# STM32.net
KiCad netlist of a schematic drawn in Altium Designer
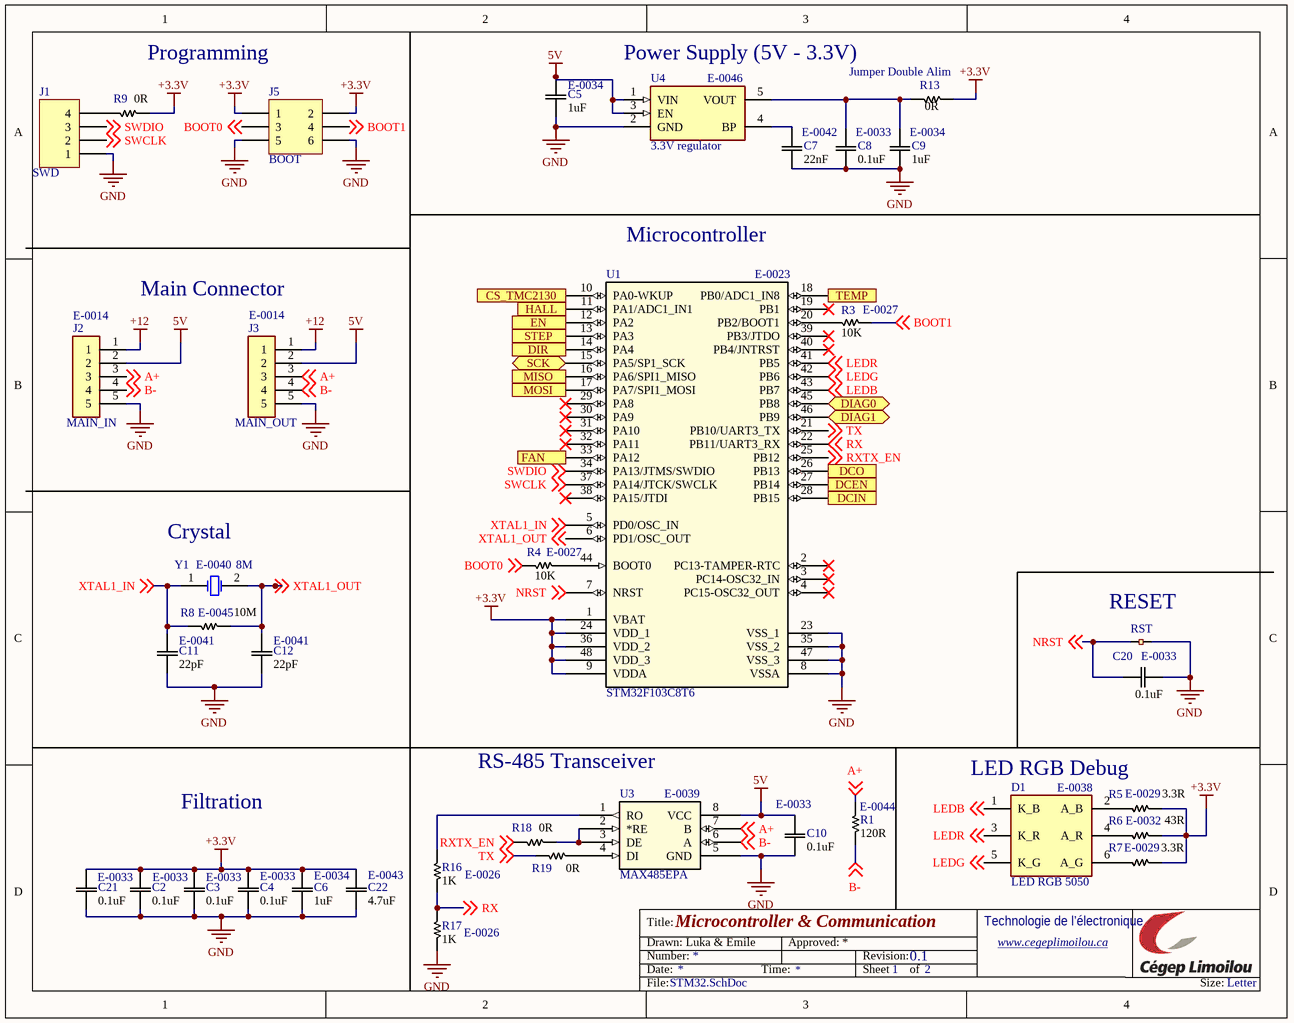
[diagram p0: STM32.SchDoc]

(export (version "E")
  (design (tool "Eeschema 10.0.6"))
  (components
    (comp (ref "C2")
      (value "0.1uF")
      (footprint "0603")
      (description "0.1uF Capacitor 0603 SMD")
      (fields
        (field (name "MANUFACTURER_PART_NUMBER") "C0603C104Z3VACTU")
        (field (name "EXCEL NUMBER") "E-0033")
        (field (name "Comment") "E-0033")
        (field (name "COPYRIGHT") "Luka & Émile")
      )
      (libsource (lib "Motor Driver") (part "E-0033"))
    )
    (comp (ref "C3")
      (value "0.1uF")
      (footprint "0603")
      (description "0.1uF Capacitor 0603 SMD")
      (fields
        (field (name "MANUFACTURER_PART_NUMBER") "C0603C104Z3VACTU")
        (field (name "EXCEL NUMBER") "E-0033")
        (field (name "Comment") "E-0033")
        (field (name "COPYRIGHT") "Luka & Émile")
      )
      (libsource (lib "Motor Driver") (part "E-0033"))
    )
    (comp (ref "C4")
      (value "0.1uF")
      (footprint "0603")
      (description "0.1uF Capacitor 0603 SMD")
      (fields
        (field (name "MANUFACTURER_PART_NUMBER") "C0603C104Z3VACTU")
        (field (name "EXCEL NUMBER") "E-0033")
        (field (name "Comment") "E-0033")
        (field (name "COPYRIGHT") "Luka & Émile")
      )
      (libsource (lib "Motor Driver") (part "E-0033"))
    )
    (comp (ref "C5")
      (value "1uF")
      (footprint "0603")
      (description "1uf Capacitor 0603 SMD")
      (fields
        (field (name "MANUFACTURER_PART_NUMBER") "CL10A105KA8NNNC")
        (field (name "EXCEL NUMBER") "E-0034")
        (field (name "Comment") "E-0034")
        (field (name "COPYRIGHT") "Luka & Émile")
      )
      (libsource (lib "Motor Driver") (part "E-0034"))
    )
    (comp (ref "C6")
      (value "1uF")
      (footprint "0603")
      (description "1uf Capacitor 0603 SMD")
      (fields
        (field (name "MANUFACTURER_PART_NUMBER") "CL10A105KA8NNNC")
        (field (name "EXCEL NUMBER") "E-0034")
        (field (name "Comment") "E-0034")
        (field (name "COPYRIGHT") "Luka & Émile")
      )
      (libsource (lib "Motor Driver") (part "E-0034"))
    )
    (comp (ref "C7")
      (value "22nF")
      (footprint "0603")
      (description "22nF Capacitor 0603 SMD")
      (fields
        (field (name "MANUFACTURER_PART_NUMBER") "C0603C223K1RACTU")
        (field (name "EXCEL NUMBER") "E-0042")
        (field (name "Comment") "E-0042")
        (field (name "COPYRIGHT") "Luka & Émile")
      )
      (libsource (lib "Motor Driver") (part "E-0042"))
    )
    (comp (ref "C8")
      (value "0.1uF")
      (footprint "0603")
      (description "0.1uF Capacitor 0603 SMD")
      (fields
        (field (name "MANUFACTURER_PART_NUMBER") "C0603C104Z3VACTU")
        (field (name "EXCEL NUMBER") "E-0033")
        (field (name "Comment") "E-0033")
        (field (name "COPYRIGHT") "Luka & Émile")
      )
      (libsource (lib "Motor Driver") (part "E-0033"))
    )
    (comp (ref "C9")
      (value "1uF")
      (footprint "0603")
      (description "1uf Capacitor 0603 SMD")
      (fields
        (field (name "MANUFACTURER_PART_NUMBER") "CL10A105KA8NNNC")
        (field (name "EXCEL NUMBER") "E-0034")
        (field (name "Comment") "E-0034")
        (field (name "COPYRIGHT") "Luka & Émile")
      )
      (libsource (lib "Motor Driver") (part "E-0034"))
    )
    (comp (ref "C10")
      (value "0.1uF")
      (footprint "0603")
      (description "0.1uF Capacitor 0603 SMD")
      (fields
        (field (name "MANUFACTURER_PART_NUMBER") "C0603C104Z3VACTU")
        (field (name "EXCEL NUMBER") "E-0033")
        (field (name "Comment") "E-0033")
        (field (name "COPYRIGHT") "Luka & Émile")
      )
      (libsource (lib "Motor Driver") (part "E-0033"))
    )
    (comp (ref "C11")
      (value "22pF")
      (footprint "0603")
      (description "22pF Capacitor 0603 SMD")
      (fields
        (field (name "MANUFACTURER_PART_NUMBER") "C0603C220J1GACTU")
        (field (name "EXCEL NUMBER") "E-0041")
        (field (name "Comment") "E-0041")
        (field (name "COPYRIGHT") "Luka & Émile")
      )
      (libsource (lib "Motor Driver") (part "E-0041"))
    )
    (comp (ref "C12")
      (value "22pF")
      (footprint "0603")
      (description "22pF Capacitor 0603 SMD")
      (fields
        (field (name "MANUFACTURER_PART_NUMBER") "C0603C220J1GACTU")
        (field (name "EXCEL NUMBER") "E-0041")
        (field (name "Comment") "E-0041")
        (field (name "COPYRIGHT") "Luka & Émile")
      )
      (libsource (lib "Motor Driver") (part "E-0041"))
    )
    (comp (ref "C20")
      (value "0.1uF")
      (footprint "0603")
      (description "0.1uF Capacitor 0603 SMD")
      (fields
        (field (name "MANUFACTURER_PART_NUMBER") "C0603C104Z3VACTU")
        (field (name "EXCEL NUMBER") "E-0033")
        (field (name "Comment") "E-0033")
        (field (name "COPYRIGHT") "Luka & Émile")
      )
      (libsource (lib "Motor Driver") (part "E-0033"))
    )
    (comp (ref "C21")
      (value "0.1uF")
      (footprint "0603")
      (description "0.1uF Capacitor 0603 SMD")
      (fields
        (field (name "MANUFACTURER_PART_NUMBER") "C0603C104Z3VACTU")
        (field (name "EXCEL NUMBER") "E-0033")
        (field (name "Comment") "E-0033")
        (field (name "COPYRIGHT") "Luka & Émile")
      )
      (libsource (lib "Motor Driver") (part "E-0033"))
    )
    (comp (ref "C22")
      (value "4.7uF")
      (footprint "0603")
      (description "4.7uF Capacitor 0603 SMD")
      (fields
        (field (name "MANUFACTURER_PART_NUMBER") "C0603C475K9PACTU")
        (field (name "EXCEL NUMBER") "E-0043")
        (field (name "Comment") "E-0043")
        (field (name "COPYRIGHT") "Luka & Émile")
      )
      (libsource (lib "Motor Driver") (part "E-0043"))
    )
    (comp (ref "D1")
      (value "LED RGB 5050")
      (footprint "LED 5050")
      (fields
        (field (name "MANUFACTURER_PART_NUMBER") "150505M173300")
        (field (name "EXCEL NUMBER") "E-0038")
        (field (name "COPYRIGHT") "Luka & Émile")
      )
      (libsource (lib "Motor Driver") (part "E-0038"))
    )
    (comp (ref "J1")
      (value "SWD")
      (footprint "HDR1X4")
      (description "Header, 4POS")
      (fields
        (field (name "MANUFACTURER_PART_NUMBER") "61300411121")
        (field (name "COPYRIGHT") "Luka & Émile")
      )
      (libsource (lib "Motor Driver") (part "E-0048"))
    )
    (comp (ref "J2")
      (value "MAIN_IN")
      (footprint "JST 5POS 2.5mm 90°")
      (description "Connector JST 5POS")
      (fields
        (field (name "MANUFACTURER_PART_NUMBER") "S5B-XH-A-1(LF)(SN)")
        (field (name "EXCEL NUMBER") "E-0014")
        (field (name "COPYRIGHT") "Luka & Émile")
      )
      (libsource (lib "Motor Driver") (part "E-0014"))
    )
    (comp (ref "J3")
      (value "MAIN_OUT")
      (footprint "JST 5POS 2.5mm 90°")
      (description "Connector JST 5POS")
      (fields
        (field (name "MANUFACTURER_PART_NUMBER") "S5B-XH-A-1(LF)(SN)")
        (field (name "EXCEL NUMBER") "E-0014")
        (field (name "COPYRIGHT") "Luka & Émile")
      )
      (libsource (lib "Motor Driver") (part "E-0014"))
    )
    (comp (ref "J5")
      (value "BOOT")
      (footprint "Header 3x2 1.27mm SMD")
      (description "Header, 3-Pin, Dual row")
      (fields
        (field (name "MANUFACTURER_PART_NUMBER") "GRPB032VWVN-RC")
        (field (name "COPYRIGHT") "Luka & Émile")
      )
      (libsource (lib "Motor Driver") (part "E-0049"))
    )
    (comp (ref "R1")
      (value "120R")
      (footprint "0603")
      (description "120R Resistor 0603 SMD")
      (fields
        (field (name "MANUFACTURER_PART_NUMBER") "KDV06FR120ET")
        (field (name "EXCEL NUMBER") "E-0044")
        (field (name "Comment") "E-0044")
        (field (name "COPYRIGHT") "Luka & Émile")
      )
      (libsource (lib "Motor Driver") (part "E-0044"))
    )
    (comp (ref "R3")
      (value "10K")
      (footprint "0603")
      (description "10K Resistor 0603 SMD")
      (fields
        (field (name "MANUFACTURER_PART_NUMBER") "RMCF0603JT10K0")
        (field (name "EXCEL NUMBER") "E-0027")
        (field (name "Comment") "E-0027")
        (field (name "COPYRIGHT") "Luka & Émile")
      )
      (libsource (lib "Motor Driver") (part "E-0027"))
    )
    (comp (ref "R4")
      (value "10K")
      (footprint "0603")
      (description "10K Resistor 0603 SMD")
      (fields
        (field (name "MANUFACTURER_PART_NUMBER") "RMCF0603JT10K0")
        (field (name "EXCEL NUMBER") "E-0027")
        (field (name "Comment") "Resistor 0603")
        (field (name "COPYRIGHT") "Luka & Émile")
      )
      (libsource (lib "Motor Driver") (part "E-0027"))
    )
    (comp (ref "R5")
      (value "3.3R")
      (footprint "0603")
      (description "3.3R Resistor 0603 SMD")
      (fields
        (field (name "MANUFACTURER_PART_NUMBER") "MCR03ERTJ3R3")
        (field (name "EXCEL NUMBER") "E-0029")
        (field (name "Comment") "E-0029")
        (field (name "COPYRIGHT") "Luka & Émile")
      )
      (libsource (lib "Motor Driver") (part "E-0029"))
    )
    (comp (ref "R6")
      (value "43R")
      (footprint "0603")
      (description "43R Resistor 0603 SMD")
      (fields
        (field (name "MANUFACTURER_PART_NUMBER") "RK73B1JTTD430J")
        (field (name "EXCEL NUMBER") "E-0032")
        (field (name "Comment") "E-0032")
        (field (name "COPYRIGHT") "Luka & Émile")
      )
      (libsource (lib "Motor Driver") (part "E-0032"))
    )
    (comp (ref "R7")
      (value "3.3R")
      (footprint "0603")
      (description "3.3R Resistor 0603 SMD")
      (fields
        (field (name "MANUFACTURER_PART_NUMBER") "MCR03ERTJ3R3")
        (field (name "EXCEL NUMBER") "E-0029")
        (field (name "Comment") "E-0029")
        (field (name "COPYRIGHT") "Luka & Émile")
      )
      (libsource (lib "Motor Driver") (part "E-0029"))
    )
    (comp (ref "R8")
      (value "10M")
      (footprint "0603")
      (description "10M Resistor 0603 SMD")
      (fields
        (field (name "MANUFACTURER_PART_NUMBER") "CRCW060310M0FKEAC")
        (field (name "EXCEL NUMBER") "E-0045")
        (field (name "Comment") "E-0045")
        (field (name "COPYRIGHT") "Luka & Émile")
      )
      (libsource (lib "Motor Driver") (part "E-0045"))
    )
    (comp (ref "R9")
      (value "0R")
      (footprint "0603")
      (description "Jumper 0603")
      (fields (field (name "Comment") "Jumper") (field (name "COPYRIGHT") "Luka & Émile"))
      (libsource (lib "Motor Driver") (part "Jumper"))
    )
    (comp (ref "R13")
      (value "0R")
      (footprint "0603")
      (description "Jumper 0603")
      (fields (field (name "Comment") "Jumper") (field (name "COPYRIGHT") "Luka & Émile"))
      (libsource (lib "Motor Driver") (part "Jumper"))
    )
    (comp (ref "R16")
      (value "1K")
      (footprint "0603")
      (description "1K Resistor 0603 SMD")
      (fields
        (field (name "MANUFACTURER_PART_NUMBER") "RK73B1JTTD102J")
        (field (name "EXCEL NUMBER") "E-0026")
        (field (name "Comment") "E-0026")
        (field (name "COPYRIGHT") "Luka & Émile")
      )
      (libsource (lib "Motor Driver") (part "E-0026"))
    )
    (comp (ref "R17")
      (value "1K")
      (footprint "0603")
      (description "1K Resistor 0603 SMD")
      (fields
        (field (name "MANUFACTURER_PART_NUMBER") "RK73B1JTTD102J")
        (field (name "EXCEL NUMBER") "E-0026")
        (field (name "Comment") "E-0026")
        (field (name "COPYRIGHT") "Luka & Émile")
      )
      (libsource (lib "Motor Driver") (part "E-0026"))
    )
    (comp (ref "R18")
      (value "0R")
      (footprint "0603")
      (description "Jumper 0603")
      (fields (field (name "Comment") "Jumper") (field (name "COPYRIGHT") "Luka & Émile"))
      (libsource (lib "Motor Driver") (part "Jumper"))
    )
    (comp (ref "R19")
      (value "0R")
      (footprint "0603")
      (description "Jumper 0603")
      (fields (field (name "Comment") "Jumper") (field (name "COPYRIGHT") "Luka & Émile"))
      (libsource (lib "Motor Driver") (part "Jumper"))
    )
    (comp (ref "RST")
      (value "~")
      (footprint "PAD")
      (description "SMD Pad for contact")
      (fields (field (name "COPYRIGHT") "Luka & Émile"))
      (libsource (lib "Motor Driver") (part "PAD"))
    )
    (comp (ref "U1")
      (value "STM32F103C8T6")
      (footprint "LQFP-48")
      (description "STM32F103C8T6 Bluepill")
      (fields
        (field (name "MANUFACTURER_PART_NUMBER") "STM32F103C8T6TR")
        (field (name "EXCEL NUMBER") "E-0023")
        (field (name "COPYRIGHT") "Luka & Émile")
      )
      (libsource (lib "Motor Driver") (part "E-0023"))
    )
    (comp (ref "U3")
      (value "MAX485EPA")
      (footprint "DIP 8 - 3D")
      (description "RS485 Communication")
      (fields
        (field (name "MANUFACTURER_PART_NUMBER") "MAX485CPA+")
        (field (name "EXCEL NUMBER") "E-0039")
        (field (name "COPYRIGHT") "Luka & Émile")
      )
      (libsource (lib "Motor Driver") (part "E-0039"))
    )
    (comp (ref "U4")
      (value "3.3V regulator")
      (footprint "SamacSys:SOT94P279X130-5N")
      (description "Voltage Regulator 3.3V SOT-23-5")
      (fields
        (field (name "MANUFACTURER_PART_NUMBER") "RT9193-28GB")
        (field (name "EXCEL NUMBER") "E-0046")
        (field (name "COPYRIGHT") "Luka & Émile")
      )
      (libsource (lib "Motor Driver") (part "E-0046"))
    )
    (comp (ref "Y1")
      (value "8M")
      (footprint "ATS080B-E")
      (description "Crystal 8M")
      (fields
        (field (name "MANUFACTURER_PART_NUMBER") "ATS080B-E")
        (field (name "EXCEL NUMBER") "E-0040")
        (field (name "COPYRIGHT") "Luka & Émile")
      )
      (libsource (lib "Motor Driver") (part "E-0040"))
    )
  )
  (nets
    (net (code "1") (name "+3.3V") (class "Default")
      (node (ref "C2") (pin "2") (pinfunction "2_2") (pintype "passive"))
      (node (ref "C21") (pin "2") (pinfunction "2_2") (pintype "passive"))
      (node (ref "C22") (pin "2") (pinfunction "2_2") (pintype "passive"))
      (node (ref "C3") (pin "2") (pinfunction "2_2") (pintype "passive"))
      (node (ref "C4") (pin "2") (pinfunction "2_2") (pintype "passive"))
      (node (ref "C6") (pin "2") (pinfunction "2_2") (pintype "passive"))
      (node (ref "J5") (pin "1") (pinfunction "1_1") (pintype "passive"))
      (node (ref "J5") (pin "2") (pinfunction "2_2") (pintype "passive"))
      (node (ref "R13") (pin "2") (pinfunction "2_2") (pintype "passive"))
      (node (ref "R5") (pin "2") (pinfunction "2_2") (pintype "passive"))
      (node (ref "R6") (pin "2") (pinfunction "2_2") (pintype "passive"))
      (node (ref "R7") (pin "2") (pinfunction "2_2") (pintype "passive"))
      (node (ref "R9") (pin "2") (pinfunction "2_2") (pintype "passive"))
      (node (ref "U1") (pin "1") (pinfunction "VBAT_1") (pintype "power_in"))
      (node (ref "U1") (pin "24") (pinfunction "VDD_1_24") (pintype "power_in"))
      (node (ref "U1") (pin "36") (pinfunction "VDD_2_36") (pintype "power_in"))
      (node (ref "U1") (pin "48") (pinfunction "VDD_3_48") (pintype "power_in"))
      (node (ref "U1") (pin "9") (pinfunction "VDDA_9") (pintype "power_in"))
    )
    (net (code "2") (name "+12") (class "Default")
      (node (ref "J2") (pin "1") (pinfunction "1_1") (pintype "passive"))
      (node (ref "J3") (pin "1") (pinfunction "1_1") (pintype "passive"))
    )
    (net (code "3") (name "/CS_TMC2130") (class "Default")
      (node (ref "U1") (pin "10") (pinfunction "PA0-WKUP_10") (pintype "bidirectional"))
    )
    (net (code "4") (name "/DCEN") (class "Default")
      (node (ref "U1") (pin "27") (pinfunction "PB14_27") (pintype "bidirectional"))
    )
    (net (code "5") (name "/DCIN") (class "Default")
      (node (ref "U1") (pin "28") (pinfunction "PB15_28") (pintype "bidirectional"))
    )
    (net (code "6") (name "/DCO") (class "Default")
      (node (ref "U1") (pin "26") (pinfunction "PB13_26") (pintype "bidirectional"))
    )
    (net (code "7") (name "/DIAG0") (class "Default")
      (node (ref "U1") (pin "45") (pinfunction "PB8_45") (pintype "bidirectional"))
    )
    (net (code "8") (name "/DIAG1") (class "Default")
      (node (ref "U1") (pin "46") (pinfunction "PB9_46") (pintype "bidirectional"))
    )
    (net (code "9") (name "/DIR") (class "Default")
      (node (ref "U1") (pin "14") (pinfunction "PA4_14") (pintype "bidirectional"))
    )
    (net (code "10") (name "/EN") (class "Default")
      (node (ref "U1") (pin "12") (pinfunction "PA2_12") (pintype "bidirectional"))
    )
    (net (code "11") (name "/FAN") (class "Default")
      (node (ref "U1") (pin "33") (pinfunction "PA12_33") (pintype "bidirectional"))
    )
    (net (code "12") (name "/HALL") (class "Default")
      (node (ref "U1") (pin "11") (pinfunction "PA1/ADC1_IN1_11") (pintype "bidirectional"))
    )
    (net (code "13") (name "/MISO") (class "Default")
      (node (ref "U1") (pin "16") (pinfunction "PA6/SPI1_MISO_16") (pintype "bidirectional"))
    )
    (net (code "14") (name "/MOSI") (class "Default")
      (node (ref "U1") (pin "17") (pinfunction "PA7/SPI1_MOSI_17") (pintype "bidirectional"))
    )
    (net (code "15") (name "/SCK") (class "Default")
      (node (ref "U1") (pin "15") (pinfunction "PA5/SP1_SCK_15") (pintype "bidirectional"))
    )
    (net (code "16") (name "/STEP") (class "Default")
      (node (ref "U1") (pin "13") (pinfunction "PA3_13") (pintype "bidirectional"))
    )
    (net (code "17") (name "/TEMP") (class "Default")
      (node (ref "U1") (pin "18") (pinfunction "PB0/ADC1_IN8_18") (pintype "bidirectional"))
    )
    (net (code "18") (name "5V") (class "Default")
      (node (ref "C10") (pin "2") (pinfunction "2_2") (pintype "passive"))
      (node (ref "C5") (pin "2") (pinfunction "2_2") (pintype "passive"))
      (node (ref "J2") (pin "2") (pinfunction "2_2") (pintype "passive"))
      (node (ref "J3") (pin "2") (pinfunction "2_2") (pintype "passive"))
      (node (ref "U3") (pin "8") (pinfunction "VCC_8") (pintype "power_in"))
      (node (ref "U4") (pin "1") (pinfunction "VIN_1") (pintype "input"))
      (node (ref "U4") (pin "3") (pinfunction "EN_3") (pintype "input"))
    )
    (net (code "19") (name "A+") (class "Default")
      (node (ref "J2") (pin "3") (pinfunction "3_3") (pintype "passive"))
      (node (ref "J3") (pin "3") (pinfunction "3_3") (pintype "passive"))
      (node (ref "R1") (pin "2") (pinfunction "2_2") (pintype "passive"))
      (node (ref "U3") (pin "7") (pinfunction "B_7") (pintype "bidirectional"))
    )
    (net (code "20") (name "B-") (class "Default")
      (node (ref "J2") (pin "4") (pinfunction "4_4") (pintype "passive"))
      (node (ref "J3") (pin "4") (pinfunction "4_4") (pintype "passive"))
      (node (ref "R1") (pin "1") (pinfunction "1_1") (pintype "passive"))
      (node (ref "U3") (pin "6") (pinfunction "A_6") (pintype "bidirectional"))
    )
    (net (code "21") (name "BOOT0") (class "Default")
      (node (ref "J5") (pin "3") (pinfunction "3_3") (pintype "passive"))
      (node (ref "R4") (pin "1") (pinfunction "1_1") (pintype "passive"))
    )
    (net (code "22") (name "BOOT1") (class "Default")
      (node (ref "J5") (pin "4") (pinfunction "4_4") (pintype "passive"))
      (node (ref "R3") (pin "2") (pinfunction "2_2") (pintype "passive"))
    )
    (net (code "23") (name "GND") (class "Default")
      (node (ref "C10") (pin "1") (pinfunction "1_1") (pintype "passive"))
      (node (ref "C11") (pin "1") (pinfunction "1_1") (pintype "passive"))
      (node (ref "C12") (pin "1") (pinfunction "1_1") (pintype "passive"))
      (node (ref "C2") (pin "1") (pinfunction "1_1") (pintype "passive"))
      (node (ref "C20") (pin "1") (pinfunction "1_1") (pintype "passive"))
      (node (ref "C21") (pin "1") (pinfunction "1_1") (pintype "passive"))
      (node (ref "C22") (pin "1") (pinfunction "1_1") (pintype "passive"))
      (node (ref "C3") (pin "1") (pinfunction "1_1") (pintype "passive"))
      (node (ref "C4") (pin "1") (pinfunction "1_1") (pintype "passive"))
      (node (ref "C5") (pin "1") (pinfunction "1_1") (pintype "passive"))
      (node (ref "C6") (pin "1") (pinfunction "1_1") (pintype "passive"))
      (node (ref "C7") (pin "1") (pinfunction "1_1") (pintype "passive"))
      (node (ref "C8") (pin "1") (pinfunction "1_1") (pintype "passive"))
      (node (ref "C9") (pin "1") (pinfunction "1_1") (pintype "passive"))
      (node (ref "J1") (pin "1") (pinfunction "1_1") (pintype "passive"))
      (node (ref "J2") (pin "5") (pinfunction "5_5") (pintype "passive"))
      (node (ref "J3") (pin "5") (pinfunction "5_5") (pintype "passive"))
      (node (ref "J5") (pin "5") (pinfunction "5_5") (pintype "passive"))
      (node (ref "J5") (pin "6") (pinfunction "6_6") (pintype "passive"))
      (node (ref "R17") (pin "2") (pinfunction "2_2") (pintype "passive"))
      (node (ref "RST") (pin "1") (pinfunction "1_1") (pintype "passive"))
      (node (ref "U1") (pin "23") (pinfunction "VSS_1_23") (pintype "power_in"))
      (node (ref "U1") (pin "35") (pinfunction "VSS_2_35") (pintype "power_in"))
      (node (ref "U1") (pin "47") (pinfunction "VSS_3_47") (pintype "power_in"))
      (node (ref "U1") (pin "8") (pinfunction "VSSA_8") (pintype "power_in"))
      (node (ref "U3") (pin "5") (pinfunction "GND_5") (pintype "power_in"))
      (node (ref "U4") (pin "2") (pinfunction "GND_2") (pintype "power_in"))
    )
    (net (code "24") (name "LEDB") (class "Default")
      (node (ref "D1") (pin "1") (pinfunction "K_B_1") (pintype "passive"))
      (node (ref "U1") (pin "43") (pinfunction "PB7_43") (pintype "bidirectional"))
    )
    (net (code "25") (name "LEDG") (class "Default")
      (node (ref "D1") (pin "5") (pinfunction "K_G_5") (pintype "passive"))
      (node (ref "U1") (pin "42") (pinfunction "PB6_42") (pintype "bidirectional"))
    )
    (net (code "26") (name "LEDR") (class "Default")
      (node (ref "D1") (pin "3") (pinfunction "K_R_3") (pintype "passive"))
      (node (ref "U1") (pin "41") (pinfunction "PB5_41") (pintype "bidirectional"))
    )
    (net (code "27") (name "NRST") (class "Default")
      (node (ref "C20") (pin "2") (pinfunction "2_2") (pintype "passive"))
      (node (ref "RST") (pin "2") (pinfunction "2_2") (pintype "passive"))
      (node (ref "U1") (pin "7") (pinfunction "NRST_7") (pintype "bidirectional"))
    )
    (net (code "28") (name "Net-(D1-A_B)") (class "Default")
      (node (ref "D1") (pin "2") (pinfunction "A_B_2") (pintype "passive"))
      (node (ref "R5") (pin "1") (pinfunction "1_1") (pintype "passive"))
    )
    (net (code "29") (name "Net-(D1-A_G)") (class "Default")
      (node (ref "D1") (pin "6") (pinfunction "A_G_6") (pintype "passive"))
      (node (ref "R7") (pin "1") (pinfunction "1_1") (pintype "passive"))
    )
    (net (code "30") (name "Net-(D1-A_R)") (class "Default")
      (node (ref "D1") (pin "4") (pinfunction "A_R_4") (pintype "passive"))
      (node (ref "R6") (pin "1") (pinfunction "1_1") (pintype "passive"))
    )
    (net (code "31") (name "Net-(J1-Pad4)") (class "Default")
      (node (ref "J1") (pin "4") (pinfunction "4_4") (pintype "passive"))
      (node (ref "R9") (pin "1") (pinfunction "1_1") (pintype "passive"))
    )
    (net (code "32") (name "Net-(U1-BOOT0)") (class "Default")
      (node (ref "R4") (pin "2") (pinfunction "2_2") (pintype "passive"))
      (node (ref "U1") (pin "44") (pinfunction "BOOT0_44") (pintype "input"))
    )
    (net (code "33") (name "Net-(U1-PB2{slash}BOOT1)") (class "Default")
      (node (ref "R3") (pin "1") (pinfunction "1_1") (pintype "passive"))
      (node (ref "U1") (pin "20") (pinfunction "PB2/BOOT1_20") (pintype "bidirectional"))
    )
    (net (code "34") (name "Net-(U3-*RE)") (class "Default")
      (node (ref "R18") (pin "2") (pinfunction "2_2") (pintype "passive"))
      (node (ref "U3") (pin "2") (pinfunction "*RE_2") (pintype "input"))
      (node (ref "U3") (pin "3") (pinfunction "DE_3") (pintype "input"))
    )
    (net (code "35") (name "Net-(U3-DI)") (class "Default")
      (node (ref "R19") (pin "2") (pinfunction "2_2") (pintype "passive"))
      (node (ref "U3") (pin "4") (pinfunction "DI_4") (pintype "input"))
    )
    (net (code "36") (name "Net-(U3-RO)") (class "Default")
      (node (ref "R16") (pin "1") (pinfunction "1_1") (pintype "passive"))
      (node (ref "U3") (pin "1") (pinfunction "RO_1") (pintype "output"))
    )
    (net (code "37") (name "Net-(U4-BP)") (class "Default")
      (node (ref "C7") (pin "2") (pinfunction "2_2") (pintype "passive"))
      (node (ref "U4") (pin "4") (pinfunction "BP_4") (pintype "passive"))
    )
    (net (code "38") (name "Net-(U4-VOUT)") (class "Default")
      (node (ref "C8") (pin "2") (pinfunction "2_2") (pintype "passive"))
      (node (ref "C9") (pin "2") (pinfunction "2_2") (pintype "passive"))
      (node (ref "R13") (pin "1") (pinfunction "1_1") (pintype "passive"))
      (node (ref "U4") (pin "5") (pinfunction "VOUT_5") (pintype "passive"))
    )
    (net (code "39") (name "RX") (class "Default")
      (node (ref "R16") (pin "2") (pinfunction "2_2") (pintype "passive"))
      (node (ref "R17") (pin "1") (pinfunction "1_1") (pintype "passive"))
      (node (ref "U1") (pin "22") (pinfunction "PB11/UART3_RX_22") (pintype "bidirectional"))
    )
    (net (code "40") (name "RXTX_EN") (class "Default")
      (node (ref "R18") (pin "1") (pinfunction "1_1") (pintype "passive"))
      (node (ref "U1") (pin "25") (pinfunction "PB12_25") (pintype "bidirectional"))
    )
    (net (code "41") (name "SWCLK") (class "Default")
      (node (ref "J1") (pin "2") (pinfunction "2_2") (pintype "passive"))
      (node (ref "U1") (pin "37") (pinfunction "PA14/JTCK/SWCLK_37") (pintype "bidirectional"))
    )
    (net (code "42") (name "SWDIO") (class "Default")
      (node (ref "J1") (pin "3") (pinfunction "3_3") (pintype "passive"))
      (node (ref "U1") (pin "34") (pinfunction "PA13/JTMS/SWDIO_34") (pintype "bidirectional"))
    )
    (net (code "43") (name "TX") (class "Default")
      (node (ref "R19") (pin "1") (pinfunction "1_1") (pintype "passive"))
      (node (ref "U1") (pin "21") (pinfunction "PB10/UART3_TX_21") (pintype "bidirectional"))
    )
    (net (code "44") (name "XTAL1_IN") (class "Default")
      (node (ref "C11") (pin "2") (pinfunction "2_2") (pintype "passive"))
      (node (ref "R8") (pin "1") (pinfunction "1_1") (pintype "passive"))
      (node (ref "U1") (pin "5") (pinfunction "PD0/OSC_IN_5") (pintype "bidirectional"))
      (node (ref "Y1") (pin "1") (pinfunction "OSC1_1") (pintype "passive"))
    )
    (net (code "45") (name "XTAL1_OUT") (class "Default")
      (node (ref "C12") (pin "2") (pinfunction "2_2") (pintype "passive"))
      (node (ref "R8") (pin "2") (pinfunction "2_2") (pintype "passive"))
      (node (ref "U1") (pin "6") (pinfunction "PD1/OSC_OUT_6") (pintype "bidirectional"))
      (node (ref "Y1") (pin "2") (pinfunction "OSC2_2") (pintype "passive"))
    )
    (net (code "46") (name "unconnected-(U1-PA8-Pad29)") (class "Default")
      (node (ref "U1") (pin "29") (pinfunction "PA8_29") (pintype "bidirectional+no_connect"))
    )
    (net (code "47") (name "unconnected-(U1-PA9-Pad30)") (class "Default")
      (node (ref "U1") (pin "30") (pinfunction "PA9_30") (pintype "bidirectional+no_connect"))
    )
    (net (code "48") (name "unconnected-(U1-PA10-Pad31)") (class "Default")
      (node (ref "U1") (pin "31") (pinfunction "PA10_31") (pintype "bidirectional+no_connect"))
    )
    (net (code "49") (name "unconnected-(U1-PA11-Pad32)") (class "Default")
      (node (ref "U1") (pin "32") (pinfunction "PA11_32") (pintype "bidirectional+no_connect"))
    )
    (net (code "50") (name "unconnected-(U1-PA15{slash}JTDI-Pad38)") (class "Default")
      (node (ref "U1") (pin "38") (pinfunction "PA15/JTDI_38") (pintype "bidirectional+no_connect"))
    )
    (net (code "51") (name "unconnected-(U1-PB1-Pad19)") (class "Default")
      (node (ref "U1") (pin "19") (pinfunction "PB1_19") (pintype "bidirectional+no_connect"))
    )
    (net (code "52") (name "unconnected-(U1-PB3{slash}JTDO-Pad39)") (class "Default")
      (node (ref "U1") (pin "39") (pinfunction "PB3/JTDO_39") (pintype "bidirectional+no_connect"))
    )
    (net (code "53") (name "unconnected-(U1-PB4{slash}JNTRST-Pad40)") (class "Default")
      (node (ref "U1") (pin "40") (pinfunction "PB4/JNTRST_40") (pintype "bidirectional+no_connect"))
    )
    (net (code "54") (name "unconnected-(U1-PC13-TAMPER-RTC-Pad2)") (class "Default")
      (node (ref "U1") (pin "2") (pinfunction "PC13-TAMPER-RTC_2") (pintype "bidirectional+no_connect"))
    )
    (net (code "55") (name "unconnected-(U1-PC14-OSC32_IN-Pad3)") (class "Default")
      (node (ref "U1") (pin "3") (pinfunction "PC14-OSC32_IN_3") (pintype "bidirectional+no_connect"))
    )
    (net (code "56") (name "unconnected-(U1-PC15-OSC32_OUT-Pad4)") (class "Default")
      (node (ref "U1") (pin "4") (pinfunction "PC15-OSC32_OUT_4") (pintype "bidirectional+no_connect"))
    )
  )
)
